# Sliders.net
KiCad netlist of a schematic drawn in Altium Designer
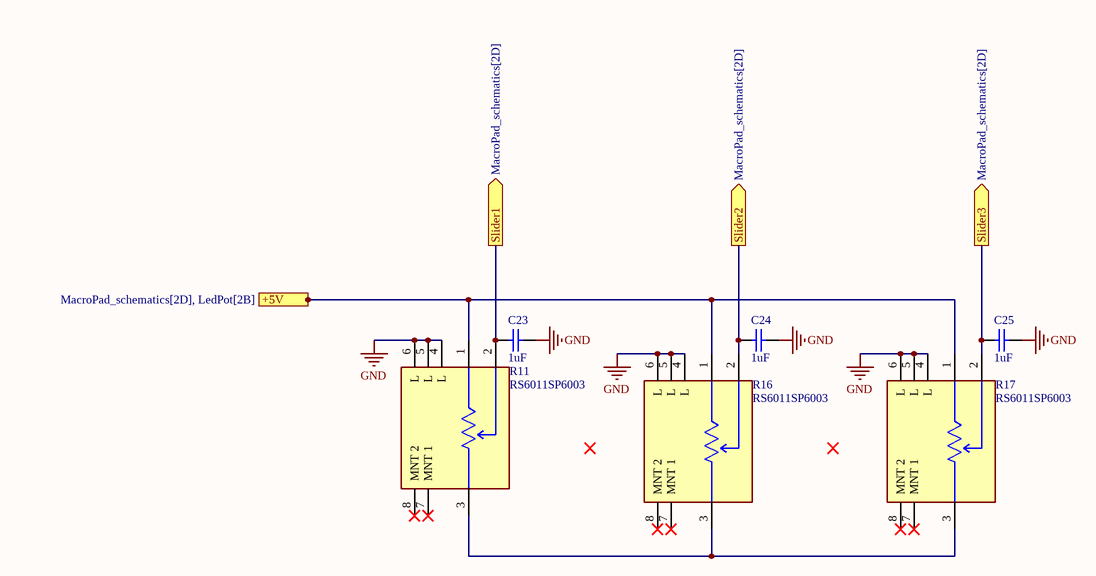
[diagram p0: Sliders.SchDoc]

(export (version "E")
  (design (tool "Eeschema 10.0.6"))
  (components
    (comp (ref "C23")
      (value "1uF")
      (footprint "KEMT-1206-2_L")
      (description "General Purpose Capacitor")
      (fields (field (name "TOLERANCE") "10%") (field (name "Comment") "1206 Capacitor"))
      (libsource (lib "EPFL Racing Team") (part "CAP"))
    )
    (comp (ref "C24")
      (value "1uF")
      (footprint "KEMT-1206-2_L")
      (description "General Purpose Capacitor")
      (fields (field (name "TOLERANCE") "10%") (field (name "Comment") "1206 Capacitor"))
      (libsource (lib "EPFL Racing Team") (part "CAP"))
    )
    (comp (ref "C25")
      (value "1uF")
      (footprint "KEMT-1206-2_L")
      (description "General Purpose Capacitor")
      (fields (field (name "TOLERANCE") "10%") (field (name "Comment") "1206 Capacitor"))
      (libsource (lib "EPFL Racing Team") (part "CAP"))
    )
    (comp (ref "R11")
      (value "RS6011SP6003")
      (footprint "FP-RS6011SP6003-MFG")
      (description "Slide Potentiometers Single Unit, 60mm Vertical Type")
      (fields (field (name "TOLERANCE") "20%"))
      (libsource (lib "Altium Content Vault") (part "d28de405ccbf2fb6327fecff9b9adee"))
    )
    (comp (ref "R16")
      (value "RS6011SP6003")
      (footprint "FP-RS6011SP6003-MFG")
      (description "Slide Potentiometers Single Unit, 60mm Vertical Type")
      (fields (field (name "TOLERANCE") "20%"))
      (libsource (lib "Altium Content Vault") (part "d28de405ccbf2fb6327fecff9b9adee"))
    )
    (comp (ref "R17")
      (value "RS6011SP6003")
      (footprint "FP-RS6011SP6003-MFG")
      (description "Slide Potentiometers Single Unit, 60mm Vertical Type")
      (fields (field (name "TOLERANCE") "20%"))
      (libsource (lib "Altium Content Vault") (part "d28de405ccbf2fb6327fecff9b9adee"))
    )
  )
  (nets
    (net (code "1") (name "/+5V") (class "Default")
      (node (ref "R11") (pin "1") (pinfunction "1_1") (pintype "passive"))
      (node (ref "R16") (pin "1") (pinfunction "1_1") (pintype "passive"))
      (node (ref "R17") (pin "1") (pinfunction "1_1") (pintype "passive"))
    )
    (net (code "2") (name "/Slider1") (class "Default")
      (node (ref "C23") (pin "2") (pinfunction "2_2") (pintype "passive"))
      (node (ref "R11") (pin "2") (pinfunction "2_2") (pintype "passive"))
    )
    (net (code "3") (name "/Slider2") (class "Default")
      (node (ref "C24") (pin "2") (pinfunction "2_2") (pintype "passive"))
      (node (ref "R16") (pin "2") (pinfunction "2_2") (pintype "passive"))
    )
    (net (code "4") (name "/Slider3") (class "Default")
      (node (ref "C25") (pin "2") (pinfunction "2_2") (pintype "passive"))
      (node (ref "R17") (pin "2") (pinfunction "2_2") (pintype "passive"))
    )
    (net (code "5") (name "GND") (class "Default")
      (node (ref "C23") (pin "1") (pinfunction "1_1") (pintype "passive"))
      (node (ref "C24") (pin "1") (pinfunction "1_1") (pintype "passive"))
      (node (ref "C25") (pin "1") (pinfunction "1_1") (pintype "passive"))
      (node (ref "R11") (pin "4") (pinfunction "L_4") (pintype "passive"))
      (node (ref "R11") (pin "5") (pinfunction "L_5") (pintype "passive"))
      (node (ref "R11") (pin "6") (pinfunction "L_6") (pintype "passive"))
      (node (ref "R16") (pin "4") (pinfunction "L_4") (pintype "passive"))
      (node (ref "R16") (pin "5") (pinfunction "L_5") (pintype "passive"))
      (node (ref "R16") (pin "6") (pinfunction "L_6") (pintype "passive"))
      (node (ref "R17") (pin "4") (pinfunction "L_4") (pintype "passive"))
      (node (ref "R17") (pin "5") (pinfunction "L_5") (pintype "passive"))
      (node (ref "R17") (pin "6") (pinfunction "L_6") (pintype "passive"))
    )
    (net (code "6") (name "Net-(R11-Pad3)") (class "Default")
      (node (ref "R11") (pin "3") (pinfunction "3_3") (pintype "passive"))
      (node (ref "R16") (pin "3") (pinfunction "3_3") (pintype "passive"))
      (node (ref "R17") (pin "3") (pinfunction "3_3") (pintype "passive"))
    )
    (net (code "7") (name "unconnected-(R11-MNT_1-Pad7)") (class "Default")
      (node (ref "R11") (pin "7") (pinfunction "MNT_1_7") (pintype "passive+no_connect"))
    )
    (net (code "8") (name "unconnected-(R11-MNT_2-Pad8)") (class "Default")
      (node (ref "R11") (pin "8") (pinfunction "MNT_2_8") (pintype "passive+no_connect"))
    )
    (net (code "9") (name "unconnected-(R16-MNT_1-Pad7)") (class "Default")
      (node (ref "R16") (pin "7") (pinfunction "MNT_1_7") (pintype "passive+no_connect"))
    )
    (net (code "10") (name "unconnected-(R16-MNT_2-Pad8)") (class "Default")
      (node (ref "R16") (pin "8") (pinfunction "MNT_2_8") (pintype "passive+no_connect"))
    )
    (net (code "11") (name "unconnected-(R17-MNT_1-Pad7)") (class "Default")
      (node (ref "R17") (pin "7") (pinfunction "MNT_1_7") (pintype "passive+no_connect"))
    )
    (net (code "12") (name "unconnected-(R17-MNT_2-Pad8)") (class "Default")
      (node (ref "R17") (pin "8") (pinfunction "MNT_2_8") (pintype "passive+no_connect"))
    )
  )
)
